# EBN_KL27Z4_V05.net
KiCad netlist of a schematic drawn in EAGLE
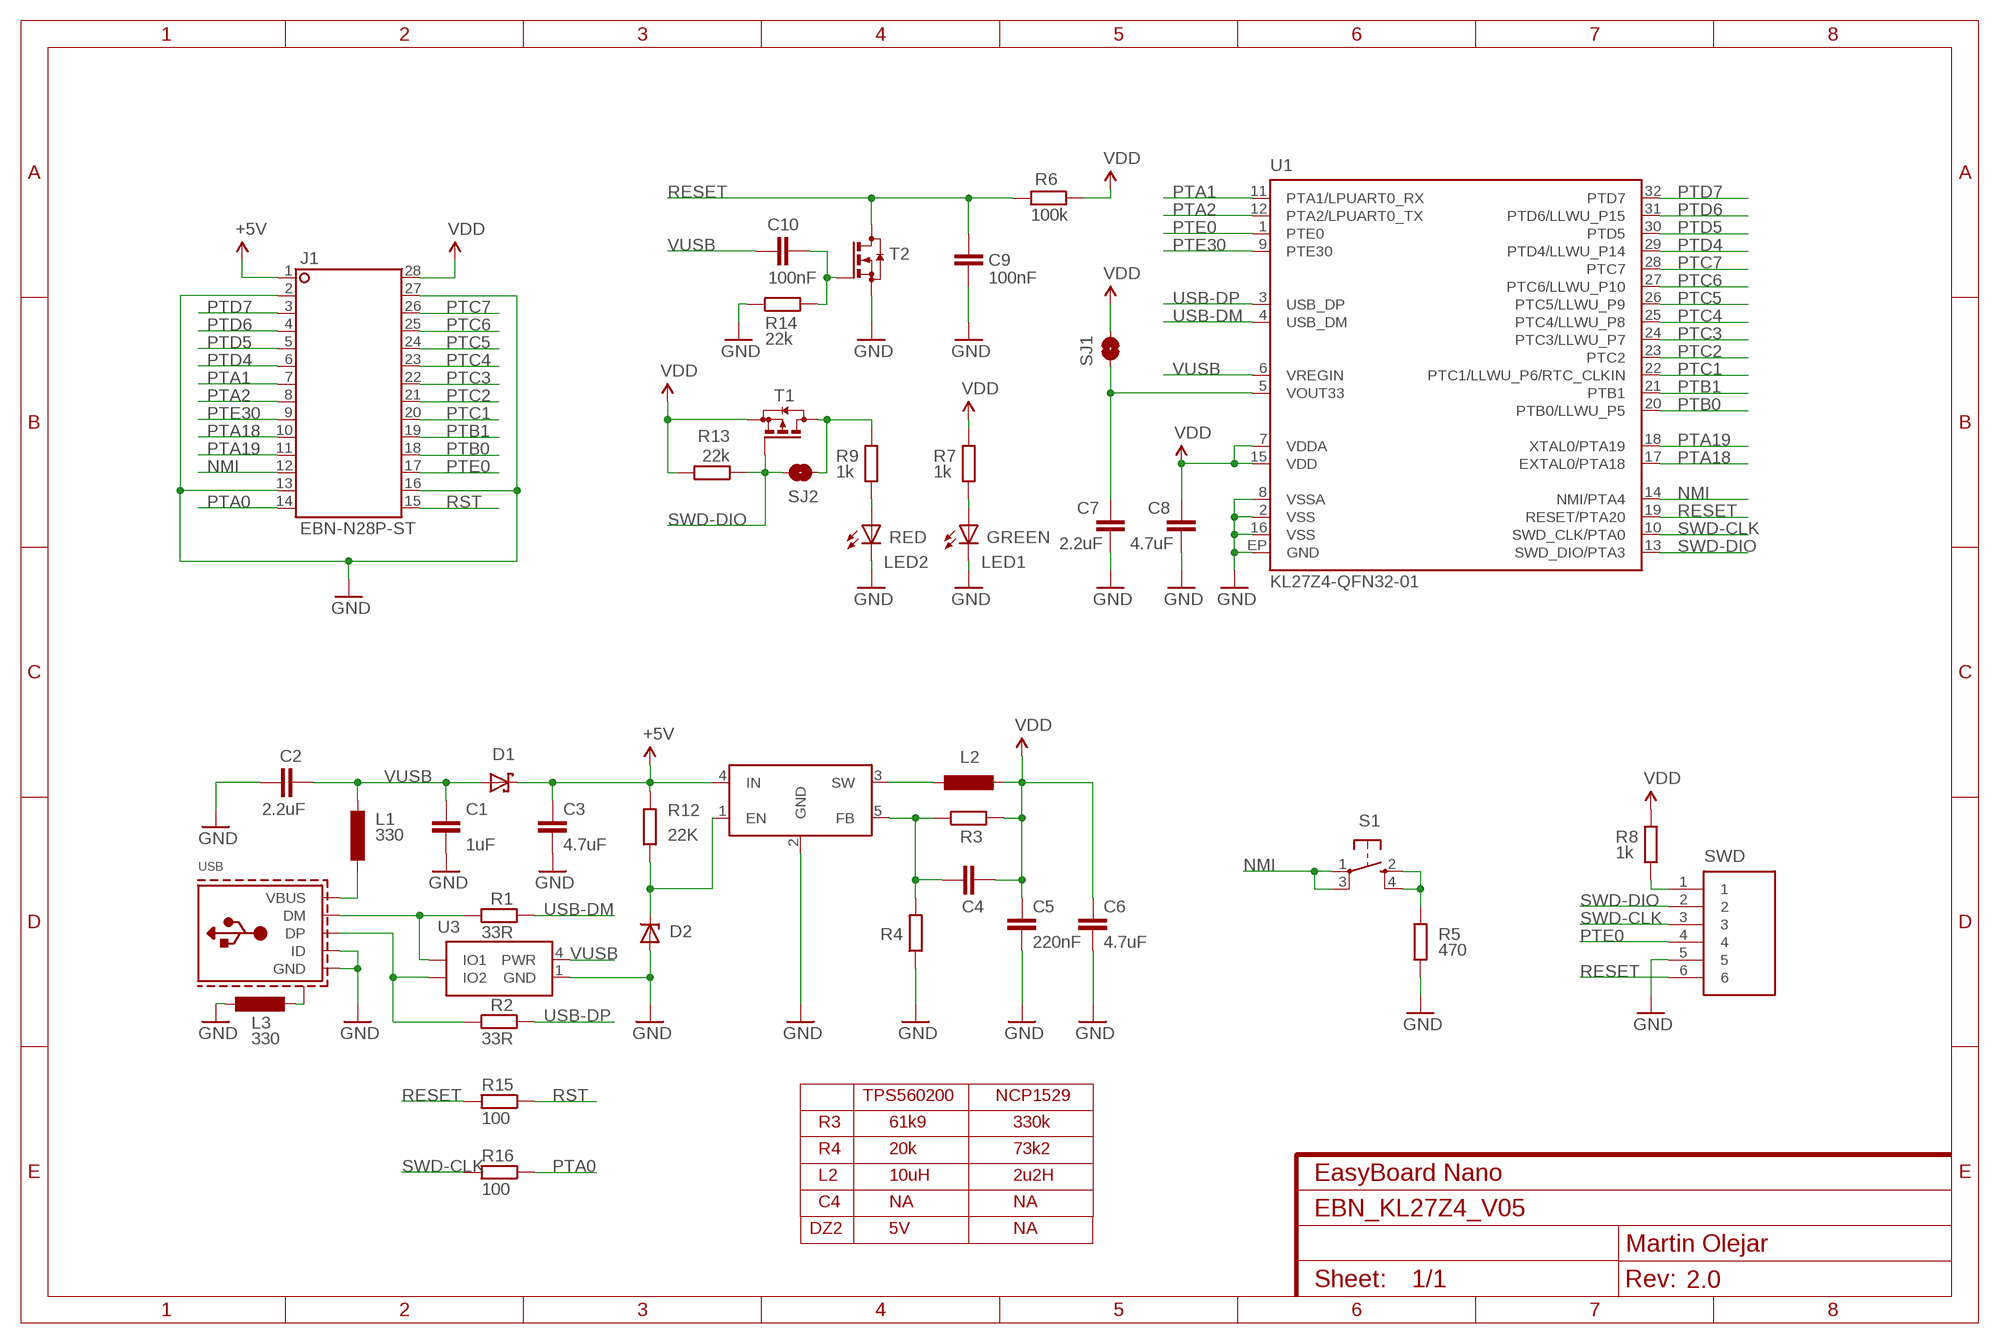
[diagram p0: schematic, sheet 1]

(export (version "E")
  (design (tool "Eeschema 10.0.6"))
  (components
    (comp (ref "C1")
      (value "1uF")
      (footprint "eagle-import:C0402")
      (libsource (lib "eagle-import") (part "C-EUC0402"))
    )
    (comp (ref "C2")
      (value "2.2uF")
      (footprint "eagle-import:C0603")
      (libsource (lib "eagle-import") (part "C-EUC0603"))
    )
    (comp (ref "C3")
      (value "4.7uF")
      (footprint "eagle-import:C0603")
      (libsource (lib "eagle-import") (part "C-EUC0603"))
    )
    (comp (ref "C4")
      (value "*")
      (footprint "eagle-import:C0402")
      (libsource (lib "eagle-import") (part "C-EUC0402"))
    )
    (comp (ref "C5")
      (value "220nF")
      (footprint "eagle-import:C0603")
      (libsource (lib "eagle-import") (part "C-EUC0603"))
    )
    (comp (ref "C6")
      (value "4.7uF")
      (footprint "eagle-import:C0603")
      (libsource (lib "eagle-import") (part "C-EUC0603"))
    )
    (comp (ref "C7")
      (value "2.2uF")
      (footprint "eagle-import:C0603")
      (libsource (lib "eagle-import") (part "C-EUC0603"))
    )
    (comp (ref "C8")
      (value "4.7uF")
      (footprint "eagle-import:C0603")
      (libsource (lib "eagle-import") (part "C-EUC0603"))
    )
    (comp (ref "C9")
      (value "100nF")
      (footprint "eagle-import:C0402")
      (libsource (lib "eagle-import") (part "C-EUC0402"))
    )
    (comp (ref "C10")
      (value "100nF")
      (footprint "eagle-import:C0402")
      (libsource (lib "eagle-import") (part "C-EUC0402"))
    )
    (comp (ref "D1")
      (value "PMEG2010BER_SHOTTKY-SOD123FL")
      (footprint "eagle-import:SOD-123FL")
      (libsource (lib "eagle-import") (part "_SHOTTKY-SOD123FLPMEG2010BER"))
    )
    (comp (ref "D2")
      (value "DZ")
      (footprint "eagle-import:SOD323_ST")
      (libsource (lib "eagle-import") (part "DZ"))
    )
    (comp (ref "J1")
      (value "EBN-N28P-ST")
      (footprint "eagle-import:EBN-N28P-SHIELD")
      (libsource (lib "eagle-import") (part "EBN-N28P-ST"))
    )
    (comp (ref "L1")
      (value "330")
      (footprint "eagle-import:L0805")
      (libsource (lib "eagle-import") (part "L-EUL0805"))
    )
    (comp (ref "L2")
      (value "2u2")
      (footprint "eagle-import:LPS3015")
      (libsource (lib "eagle-import") (part "L-EULPS3015"))
    )
    (comp (ref "L3")
      (value "330")
      (footprint "eagle-import:L0805")
      (libsource (lib "eagle-import") (part "L-EUL0805"))
    )
    (comp (ref "LED1")
      (value "LEDCHIPLED_0603")
      (footprint "eagle-import:CHIPLED_0603")
      (libsource (lib "eagle-import") (part "LEDCHIPLED_0603"))
    )
    (comp (ref "LED2")
      (value "LEDCHIPLED_0603")
      (footprint "eagle-import:CHIPLED_0603")
      (libsource (lib "eagle-import") (part "LEDCHIPLED_0603"))
    )
    (comp (ref "R1")
      (value "33R")
      (footprint "eagle-import:R0402")
      (libsource (lib "eagle-import") (part "R-EUR0402"))
    )
    (comp (ref "R2")
      (value "33R")
      (footprint "eagle-import:R0402")
      (libsource (lib "eagle-import") (part "R-EUR0402"))
    )
    (comp (ref "R3")
      (value "*")
      (footprint "eagle-import:R0402")
      (libsource (lib "eagle-import") (part "R-EUR0402"))
    )
    (comp (ref "R4")
      (value "*")
      (footprint "eagle-import:R0402")
      (libsource (lib "eagle-import") (part "R-EUR0402"))
    )
    (comp (ref "R5")
      (value "470")
      (footprint "eagle-import:R0402")
      (libsource (lib "eagle-import") (part "R-EUR0402"))
    )
    (comp (ref "R6")
      (value "100k")
      (footprint "eagle-import:R0402")
      (libsource (lib "eagle-import") (part "R-EUR0402"))
    )
    (comp (ref "R7")
      (value "1k")
      (footprint "eagle-import:R0402")
      (libsource (lib "eagle-import") (part "R-EUR0402"))
    )
    (comp (ref "R8")
      (value "1k")
      (footprint "eagle-import:R0402")
      (libsource (lib "eagle-import") (part "R-EUR0402"))
    )
    (comp (ref "R9")
      (value "1k")
      (footprint "eagle-import:R0402")
      (libsource (lib "eagle-import") (part "R-EUR0402"))
    )
    (comp (ref "R12")
      (value "22K")
      (footprint "eagle-import:R0603")
      (libsource (lib "eagle-import") (part "R-EUR0603"))
    )
    (comp (ref "R13")
      (value "22k")
      (footprint "eagle-import:R0402")
      (libsource (lib "eagle-import") (part "R-EUR0402"))
    )
    (comp (ref "R14")
      (value "22k")
      (footprint "eagle-import:R0402")
      (libsource (lib "eagle-import") (part "R-EUR0402"))
    )
    (comp (ref "R15")
      (value "100")
      (footprint "eagle-import:R0402")
      (libsource (lib "eagle-import") (part "R-EUR0402"))
    )
    (comp (ref "R16")
      (value "100")
      (footprint "eagle-import:R0402")
      (libsource (lib "eagle-import") (part "R-EUR0402"))
    )
    (comp (ref "S1")
      (value "SWITCH-TACT2")
      (footprint "eagle-import:KMR2")
      (libsource (lib "eagle-import") (part "SWITCH-TACT2"))
    )
    (comp (ref "SJ1")
      (value "SJ-S")
      (footprint "eagle-import:JUMPER-SMD-S1X")
      (libsource (lib "eagle-import") (part "SJ-S"))
    )
    (comp (ref "SJ2")
      (value "SJ-S")
      (footprint "eagle-import:JUMPER-SMD-S1X")
      (libsource (lib "eagle-import") (part "SJ-S"))
    )
    (comp (ref "SWD")
      (value "CON-1X6JST-SIDE")
      (footprint "eagle-import:CON-JST1X6-SIDE")
      (libsource (lib "eagle-import") (part "CON-1X6JST-SIDE"))
    )
    (comp (ref "T1")
      (value "-PMOS-SOT323")
      (footprint "eagle-import:SOT323")
      (libsource (lib "eagle-import") (part "-PMOS-SOT323"))
    )
    (comp (ref "T2")
      (value "-NMOS-SOT323")
      (footprint "eagle-import:SOT323")
      (libsource (lib "eagle-import") (part "-NMOS-SOT323"))
    )
    (comp (ref "U1")
      (value "KL27Z4-QFN32-01")
      (footprint "eagle-import:QFN-32")
      (libsource (lib "eagle-import") (part "KL27Z4-QFN32-01"))
    )
    (comp (ref "U2")
      (value "MP215P")
      (footprint "eagle-import:SOT23-5L")
      (libsource (lib "eagle-import") (part "MP215P"))
    )
    (comp (ref "U3")
      (value "PRTR5V0U2X")
      (footprint "eagle-import:SOT-143B")
      (fields
        (field (name "MANUFACTURER") "NXP Semiconductors")
        (field (name "PART_NUMBER") "PRTR5V0U2X,215")
      )
      (libsource (lib "eagle-import") (part "PRTR5V0U2X?"))
    )
    (comp (ref "USB")
      (value "USB-5P-MICRO-SMD-05")
      (footprint "eagle-import:USB-MICRO-SMD-05")
      (libsource (lib "eagle-import") (part "USB-5P-MICRO-SMD-05"))
    )
  )
  (nets
    (net (code "1") (name "+5V") (class "Default")
      (node (ref "C3") (pin "1") (pinfunction "1_1") (pintype "passive"))
      (node (ref "D1") (pin "C") (pinfunction "C_C") (pintype "passive"))
      (node (ref "J1") (pin "1") (pinfunction "1_1") (pintype "passive"))
      (node (ref "R12") (pin "2") (pinfunction "2_2") (pintype "passive"))
      (node (ref "U2") (pin "4") (pinfunction "IN_4") (pintype "power_in"))
    )
    (net (code "2") (name "/NMI") (class "Default")
      (node (ref "J1") (pin "12") (pinfunction "12_12") (pintype "passive"))
      (node (ref "S1") (pin "1") (pinfunction "1_1") (pintype "passive"))
      (node (ref "S1") (pin "3") (pinfunction "2_3") (pintype "passive"))
      (node (ref "U1") (pin "14") (pinfunction "NMI/PTA4_14") (pintype "bidirectional"))
    )
    (net (code "3") (name "/PTA0") (class "Default")
      (node (ref "J1") (pin "14") (pinfunction "14_14") (pintype "passive"))
      (node (ref "R16") (pin "1") (pinfunction "1_1") (pintype "passive"))
    )
    (net (code "4") (name "/PTA1") (class "Default")
      (node (ref "J1") (pin "7") (pinfunction "7_7") (pintype "passive"))
      (node (ref "U1") (pin "11") (pinfunction "PTA1/LPUART0_RX_11") (pintype "bidirectional"))
    )
    (net (code "5") (name "/PTA2") (class "Default")
      (node (ref "J1") (pin "8") (pinfunction "8_8") (pintype "passive"))
      (node (ref "U1") (pin "12") (pinfunction "PTA2/LPUART0_TX_12") (pintype "bidirectional"))
    )
    (net (code "6") (name "/PTA18") (class "Default")
      (node (ref "J1") (pin "10") (pinfunction "10_10") (pintype "passive"))
      (node (ref "U1") (pin "17") (pinfunction "EXTAL0/PTA18_17") (pintype "bidirectional"))
    )
    (net (code "7") (name "/PTA19") (class "Default")
      (node (ref "J1") (pin "11") (pinfunction "11_11") (pintype "passive"))
      (node (ref "U1") (pin "18") (pinfunction "XTAL0/PTA19_18") (pintype "bidirectional"))
    )
    (net (code "8") (name "/PTB0") (class "Default")
      (node (ref "J1") (pin "18") (pinfunction "18_18") (pintype "passive"))
      (node (ref "U1") (pin "20") (pinfunction "PTB0/LLWU_P5_20") (pintype "bidirectional"))
    )
    (net (code "9") (name "/PTB1") (class "Default")
      (node (ref "J1") (pin "19") (pinfunction "19_19") (pintype "passive"))
      (node (ref "U1") (pin "21") (pinfunction "PTB1_21") (pintype "bidirectional"))
    )
    (net (code "10") (name "/PTC1") (class "Default")
      (node (ref "J1") (pin "20") (pinfunction "20_20") (pintype "passive"))
      (node (ref "U1") (pin "22") (pinfunction "PTC1/LLWU_P6/RTC_CLKIN_22") (pintype "bidirectional"))
    )
    (net (code "11") (name "/PTC2") (class "Default")
      (node (ref "J1") (pin "21") (pinfunction "21_21") (pintype "passive"))
      (node (ref "U1") (pin "23") (pinfunction "PTC2_23") (pintype "bidirectional"))
    )
    (net (code "12") (name "/PTC3") (class "Default")
      (node (ref "J1") (pin "22") (pinfunction "22_22") (pintype "passive"))
      (node (ref "U1") (pin "24") (pinfunction "PTC3/LLWU_P7_24") (pintype "bidirectional"))
    )
    (net (code "13") (name "/PTC4") (class "Default")
      (node (ref "J1") (pin "23") (pinfunction "23_23") (pintype "passive"))
      (node (ref "U1") (pin "25") (pinfunction "PTC4/LLWU_P8_25") (pintype "bidirectional"))
    )
    (net (code "14") (name "/PTC5") (class "Default")
      (node (ref "J1") (pin "24") (pinfunction "24_24") (pintype "passive"))
      (node (ref "U1") (pin "26") (pinfunction "PTC5/LLWU_P9_26") (pintype "bidirectional"))
    )
    (net (code "15") (name "/PTC6") (class "Default")
      (node (ref "J1") (pin "25") (pinfunction "25_25") (pintype "passive"))
      (node (ref "U1") (pin "27") (pinfunction "PTC6/LLWU_P10_27") (pintype "bidirectional"))
    )
    (net (code "16") (name "/PTC7") (class "Default")
      (node (ref "J1") (pin "26") (pinfunction "26_26") (pintype "passive"))
      (node (ref "U1") (pin "28") (pinfunction "PTC7_28") (pintype "bidirectional"))
    )
    (net (code "17") (name "/PTD4") (class "Default")
      (node (ref "J1") (pin "6") (pinfunction "6_6") (pintype "passive"))
      (node (ref "U1") (pin "29") (pinfunction "PTD4/LLWU_P14_29") (pintype "bidirectional"))
    )
    (net (code "18") (name "/PTD5") (class "Default")
      (node (ref "J1") (pin "5") (pinfunction "5_5") (pintype "passive"))
      (node (ref "U1") (pin "30") (pinfunction "PTD5_30") (pintype "bidirectional"))
    )
    (net (code "19") (name "/PTD6") (class "Default")
      (node (ref "J1") (pin "4") (pinfunction "4_4") (pintype "passive"))
      (node (ref "U1") (pin "31") (pinfunction "PTD6/LLWU_P15_31") (pintype "bidirectional"))
    )
    (net (code "20") (name "/PTD7") (class "Default")
      (node (ref "J1") (pin "3") (pinfunction "3_3") (pintype "passive"))
      (node (ref "U1") (pin "32") (pinfunction "PTD7_32") (pintype "bidirectional"))
    )
    (net (code "21") (name "/PTE0") (class "Default")
      (node (ref "J1") (pin "17") (pinfunction "17_17") (pintype "passive"))
      (node (ref "SWD") (pin "4") (pinfunction "4_4") (pintype "bidirectional"))
      (node (ref "U1") (pin "1") (pinfunction "PTE0_1") (pintype "bidirectional"))
    )
    (net (code "22") (name "/PTE30") (class "Default")
      (node (ref "J1") (pin "9") (pinfunction "9_9") (pintype "passive"))
      (node (ref "U1") (pin "9") (pinfunction "PTE30_9") (pintype "bidirectional"))
    )
    (net (code "23") (name "/RESET") (class "Default")
      (node (ref "C9") (pin "1") (pinfunction "1_1") (pintype "passive"))
      (node (ref "R15") (pin "2") (pinfunction "2_2") (pintype "passive"))
      (node (ref "R6") (pin "2") (pinfunction "2_2") (pintype "passive"))
      (node (ref "SWD") (pin "6") (pinfunction "6_6") (pintype "bidirectional"))
      (node (ref "T2") (pin "3") (pinfunction "D_3") (pintype "passive"))
      (node (ref "U1") (pin "19") (pinfunction "RESET/PTA20_19") (pintype "bidirectional"))
    )
    (net (code "24") (name "/RST") (class "Default")
      (node (ref "J1") (pin "15") (pinfunction "15_15") (pintype "passive"))
      (node (ref "R15") (pin "1") (pinfunction "1_1") (pintype "passive"))
    )
    (net (code "25") (name "/SWD-CLK") (class "Default")
      (node (ref "R16") (pin "2") (pinfunction "2_2") (pintype "passive"))
      (node (ref "SWD") (pin "3") (pinfunction "3_3") (pintype "bidirectional"))
      (node (ref "U1") (pin "10") (pinfunction "SWD_CLK/PTA0_10") (pintype "bidirectional"))
    )
    (net (code "26") (name "/SWD-DIO") (class "Default")
      (node (ref "R13") (pin "1") (pinfunction "1_1") (pintype "passive"))
      (node (ref "SJ2") (pin "2") (pinfunction "2_2") (pintype "passive"))
      (node (ref "SWD") (pin "2") (pinfunction "2_2") (pintype "bidirectional"))
      (node (ref "T1") (pin "1") (pinfunction "G_1") (pintype "passive"))
      (node (ref "U1") (pin "13") (pinfunction "SWD_DIO/PTA3_13") (pintype "bidirectional"))
    )
    (net (code "27") (name "/USB-DM") (class "Default")
      (node (ref "R1") (pin "2") (pinfunction "2_2") (pintype "passive"))
      (node (ref "U1") (pin "4") (pinfunction "USB_DM_4") (pintype "bidirectional"))
    )
    (net (code "28") (name "/USB-DP") (class "Default")
      (node (ref "R2") (pin "2") (pinfunction "2_2") (pintype "passive"))
      (node (ref "U1") (pin "3") (pinfunction "USB_DP_3") (pintype "bidirectional"))
    )
    (net (code "29") (name "/VUSB") (class "Default")
      (node (ref "C1") (pin "2") (pinfunction "2_2") (pintype "passive"))
      (node (ref "C10") (pin "1") (pinfunction "1_1") (pintype "passive"))
      (node (ref "C2") (pin "1") (pinfunction "1_1") (pintype "passive"))
      (node (ref "D1") (pin "A") (pinfunction "A_A") (pintype "passive"))
      (node (ref "L1") (pin "2") (pinfunction "2_2") (pintype "passive"))
      (node (ref "U1") (pin "6") (pinfunction "VREGIN_6") (pintype "power_in"))
      (node (ref "U3") (pin "4") (pinfunction "PWR_4") (pintype "power_in"))
    )
    (net (code "30") (name "GND") (class "Default")
      (node (ref "C1") (pin "1") (pinfunction "1_1") (pintype "passive"))
      (node (ref "C2") (pin "2") (pinfunction "2_2") (pintype "passive"))
      (node (ref "C3") (pin "2") (pinfunction "2_2") (pintype "passive"))
      (node (ref "C5") (pin "2") (pinfunction "2_2") (pintype "passive"))
      (node (ref "C6") (pin "2") (pinfunction "2_2") (pintype "passive"))
      (node (ref "C7") (pin "2") (pinfunction "2_2") (pintype "passive"))
      (node (ref "C8") (pin "2") (pinfunction "2_2") (pintype "passive"))
      (node (ref "C9") (pin "2") (pinfunction "2_2") (pintype "passive"))
      (node (ref "D2") (pin "A") (pinfunction "A_A") (pintype "passive"))
      (node (ref "J1") (pin "13") (pinfunction "13_13") (pintype "passive"))
      (node (ref "J1") (pin "16") (pinfunction "16_16") (pintype "passive"))
      (node (ref "J1") (pin "2") (pinfunction "2_2") (pintype "passive"))
      (node (ref "J1") (pin "27") (pinfunction "27_27") (pintype "passive"))
      (node (ref "L3") (pin "2") (pinfunction "2_2") (pintype "passive"))
      (node (ref "LED1") (pin "C") (pinfunction "C_C") (pintype "passive"))
      (node (ref "LED2") (pin "C") (pinfunction "C_C") (pintype "passive"))
      (node (ref "R14") (pin "1") (pinfunction "1_1") (pintype "passive"))
      (node (ref "R4") (pin "1") (pinfunction "1_1") (pintype "passive"))
      (node (ref "R5") (pin "1") (pinfunction "1_1") (pintype "passive"))
      (node (ref "SWD") (pin "5") (pinfunction "5_5") (pintype "bidirectional"))
      (node (ref "T2") (pin "2") (pinfunction "S_2") (pintype "passive"))
      (node (ref "U1") (pin "16") (pinfunction "VSS_16") (pintype "power_in"))
      (node (ref "U1") (pin "2") (pinfunction "VSS_2") (pintype "power_in"))
      (node (ref "U1") (pin "8") (pinfunction "VSSA_8") (pintype "power_in"))
      (node (ref "U1") (pin "EP") (pinfunction "GND_EP") (pintype "power_in"))
      (node (ref "U2") (pin "2") (pinfunction "GND_2") (pintype "power_in"))
      (node (ref "U3") (pin "1") (pinfunction "GND_1") (pintype "power_in"))
      (node (ref "USB") (pin "GND") (pinfunction "GND_GND") (pintype "power_in"))
      (node (ref "USB") (pin "ID") (pinfunction "ID_ID") (pintype "bidirectional"))
    )
    (net (code "31") (name "Net-(L1-Pad1)") (class "Default")
      (node (ref "L1") (pin "1") (pinfunction "1_1") (pintype "passive"))
      (node (ref "USB") (pin "VBUS") (pinfunction "VBUS_VBUS") (pintype "power_in"))
    )
    (net (code "32") (name "Net-(L2-1)") (class "Default")
      (node (ref "L2") (pin "P$1") (pinfunction "1_P$1") (pintype "passive"))
      (node (ref "U2") (pin "3") (pinfunction "SW_3") (pintype "power_in"))
    )
    (net (code "33") (name "Net-(L3-Pad1)") (class "Default")
      (node (ref "L3") (pin "1") (pinfunction "1_1") (pintype "passive"))
      (node (ref "USB") (pin "SHILD@1") (pinfunction "SHILD_SHILD@1") (pintype "passive"))
      (node (ref "USB") (pin "SHILD@2") (pinfunction "SHILD_SHILD@2") (pintype "passive"))
      (node (ref "USB") (pin "SHILD@3") (pinfunction "SHILD_SHILD@3") (pintype "passive"))
      (node (ref "USB") (pin "SHILD@4") (pinfunction "SHILD_SHILD@4") (pintype "passive"))
    )
    (net (code "34") (name "Net-(LED1-PadA)") (class "Default")
      (node (ref "LED1") (pin "A") (pinfunction "A_A") (pintype "passive"))
      (node (ref "R7") (pin "1") (pinfunction "1_1") (pintype "passive"))
    )
    (net (code "35") (name "Net-(LED2-PadA)") (class "Default")
      (node (ref "LED2") (pin "A") (pinfunction "A_A") (pintype "passive"))
      (node (ref "R9") (pin "1") (pinfunction "1_1") (pintype "passive"))
    )
    (net (code "36") (name "Net-(R8-Pad1)") (class "Default")
      (node (ref "R8") (pin "1") (pinfunction "1_1") (pintype "passive"))
      (node (ref "SWD") (pin "1") (pinfunction "1_1") (pintype "bidirectional"))
    )
    (net (code "37") (name "Net-(S1-3)") (class "Default")
      (node (ref "R5") (pin "2") (pinfunction "2_2") (pintype "passive"))
      (node (ref "S1") (pin "2") (pinfunction "3_2") (pintype "passive"))
      (node (ref "S1") (pin "4") (pinfunction "4_4") (pintype "passive"))
    )
    (net (code "38") (name "Net-(T1-D)") (class "Default")
      (node (ref "R9") (pin "2") (pinfunction "2_2") (pintype "passive"))
      (node (ref "SJ2") (pin "1") (pinfunction "1_1") (pintype "passive"))
      (node (ref "T1") (pin "3") (pinfunction "D_3") (pintype "passive"))
    )
    (net (code "39") (name "Net-(T2-G)") (class "Default")
      (node (ref "C10") (pin "2") (pinfunction "2_2") (pintype "passive"))
      (node (ref "R14") (pin "2") (pinfunction "2_2") (pintype "passive"))
      (node (ref "T2") (pin "1") (pinfunction "G_1") (pintype "passive"))
    )
    (net (code "40") (name "Net-(U1-VOUT33)") (class "Default")
      (node (ref "C7") (pin "1") (pinfunction "1_1") (pintype "passive"))
      (node (ref "SJ1") (pin "1") (pinfunction "1_1") (pintype "passive"))
      (node (ref "U1") (pin "5") (pinfunction "VOUT33_5") (pintype "power_in"))
    )
    (net (code "41") (name "Net-(U2-EN)") (class "Default")
      (node (ref "D2") (pin "C") (pinfunction "C_C") (pintype "passive"))
      (node (ref "R12") (pin "1") (pinfunction "1_1") (pintype "passive"))
      (node (ref "U2") (pin "1") (pinfunction "EN_1") (pintype "input"))
    )
    (net (code "42") (name "Net-(U2-FB)") (class "Default")
      (node (ref "C4") (pin "1") (pinfunction "1_1") (pintype "passive"))
      (node (ref "R3") (pin "1") (pinfunction "1_1") (pintype "passive"))
      (node (ref "R4") (pin "2") (pinfunction "2_2") (pintype "passive"))
      (node (ref "U2") (pin "5") (pinfunction "FB_5") (pintype "input"))
    )
    (net (code "43") (name "Net-(U3-IO1)") (class "Default")
      (node (ref "R1") (pin "1") (pinfunction "1_1") (pintype "passive"))
      (node (ref "U3") (pin "3") (pinfunction "IO1_3") (pintype "bidirectional"))
      (node (ref "USB") (pin "DM") (pinfunction "DM_DM") (pintype "bidirectional"))
    )
    (net (code "44") (name "Net-(U3-IO2)") (class "Default")
      (node (ref "R2") (pin "1") (pinfunction "1_1") (pintype "passive"))
      (node (ref "U3") (pin "2") (pinfunction "IO2_2") (pintype "bidirectional"))
      (node (ref "USB") (pin "DP") (pinfunction "DP_DP") (pintype "bidirectional"))
    )
    (net (code "45") (name "VDD") (class "Default")
      (node (ref "C4") (pin "2") (pinfunction "2_2") (pintype "passive"))
      (node (ref "C5") (pin "1") (pinfunction "1_1") (pintype "passive"))
      (node (ref "C6") (pin "1") (pinfunction "1_1") (pintype "passive"))
      (node (ref "C8") (pin "1") (pinfunction "1_1") (pintype "passive"))
      (node (ref "J1") (pin "28") (pinfunction "28_28") (pintype "passive"))
      (node (ref "L2") (pin "P$2") (pinfunction "2_P$2") (pintype "passive"))
      (node (ref "R13") (pin "2") (pinfunction "2_2") (pintype "passive"))
      (node (ref "R3") (pin "2") (pinfunction "2_2") (pintype "passive"))
      (node (ref "R6") (pin "1") (pinfunction "1_1") (pintype "passive"))
      (node (ref "R7") (pin "2") (pinfunction "2_2") (pintype "passive"))
      (node (ref "R8") (pin "2") (pinfunction "2_2") (pintype "passive"))
      (node (ref "SJ1") (pin "2") (pinfunction "2_2") (pintype "passive"))
      (node (ref "T1") (pin "2") (pinfunction "S_2") (pintype "passive"))
      (node (ref "U1") (pin "15") (pinfunction "VDD_15") (pintype "power_in"))
      (node (ref "U1") (pin "7") (pinfunction "VDDA_7") (pintype "power_in"))
    )
  )
)
